# Harvester_Solar.net
KiCad netlist of a schematic drawn in Altium Designer
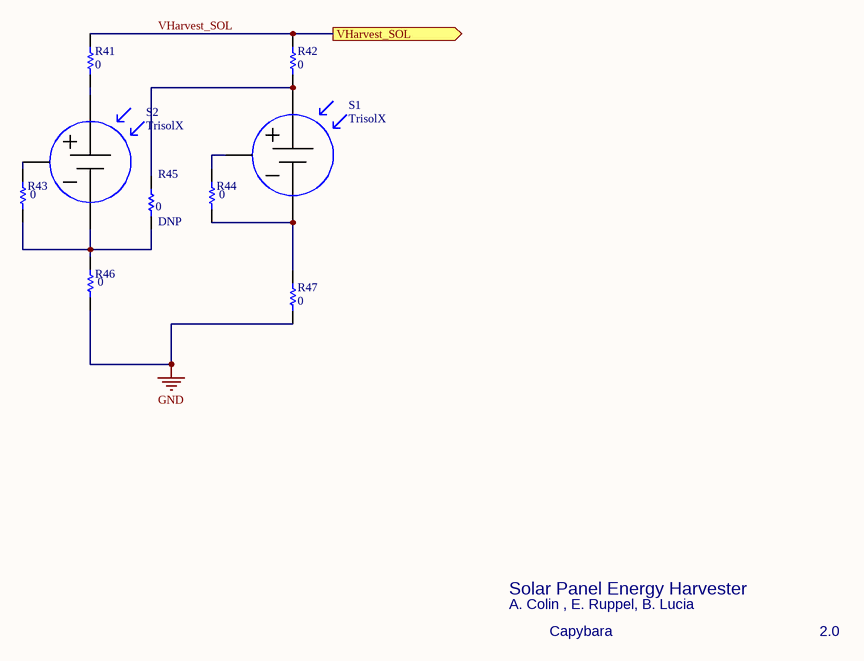
[diagram p0: Harvester_Solar.SchDoc]

(export (version "E")
  (design (tool "Eeschema 10.0.6"))
  (components
    (comp (ref "R41")
      (value "0")
      (footprint "0603")
      (description "Chip Resistor (Surface Mount)")
      (fields
        (field (name "MANUFACTURER") "Yageo")
        (field (name "MANUFACTURER PART NUMBER") "RC0603JR-070RL")
      )
      (libsource (lib "DRP_Basic_2014") (part "Res"))
    )
    (comp (ref "R42")
      (value "0")
      (footprint "0603")
      (description "Chip Resistor (Surface Mount)")
      (fields
        (field (name "MANUFACTURER") "Yageo")
        (field (name "MANUFACTURER PART NUMBER") "RC0603JR-070RL")
      )
      (libsource (lib "DRP_Basic_2014") (part "Res"))
    )
    (comp (ref "R43")
      (value "0")
      (footprint "0603")
      (description "Chip Resistor (Surface Mount)")
      (fields
        (field (name "MANUFACTURER") "Yageo")
        (field (name "MANUFACTURER PART NUMBER") "RC0603JR-070RL")
      )
      (libsource (lib "DRP_Basic_2014") (part "Res"))
    )
    (comp (ref "R44")
      (value "0")
      (footprint "0603")
      (description "Chip Resistor (Surface Mount)")
      (fields
        (field (name "MANUFACTURER") "Yageo")
        (field (name "MANUFACTURER PART NUMBER") "RC0603JR-070RL")
      )
      (libsource (lib "DRP_Basic_2014") (part "Res"))
    )
    (comp (ref "R45")
      (value "DNP")
      (footprint "0603")
      (description "Chip Resistor (Surface Mount)")
      (fields
        (field (name "MANUFACTURER") "Yageo")
        (field (name "MANUFACTURER PART NUMBER") "RC0603JR-070RL")
        (field (name "ALTIUM_VALUE") "0")
      )
      (libsource (lib "DRP_Basic_2014") (part "Res"))
    )
    (comp (ref "R46")
      (value "0")
      (footprint "0603")
      (description "Chip Resistor (Surface Mount)")
      (fields
        (field (name "MANUFACTURER") "Yageo")
        (field (name "MANUFACTURER PART NUMBER") "RC0603JR-070RL")
      )
      (libsource (lib "DRP_Basic_2014") (part "Res"))
    )
    (comp (ref "R47")
      (value "0")
      (footprint "0603")
      (description "Chip Resistor (Surface Mount)")
      (fields
        (field (name "MANUFACTURER") "Yageo")
        (field (name "MANUFACTURER PART NUMBER") "RC0603JR-070RL")
      )
      (libsource (lib "DRP_Basic_2014") (part "Res"))
    )
    (comp (ref "S1")
      (value "TrisolX")
      (footprint "TricoLX - Basic_V3_MIRROR_STRAIGHT_OR_IXYS")
      (description "TrisolX Solar Wings")
      (libsource (lib "Sprite") (part "TrisolX_Solar_Wings"))
    )
    (comp (ref "S2")
      (value "TrisolX")
      (footprint "TricoLX - Basic_V3_MIRROR_STRAIGHT_OR_IXYS")
      (description "TrisolX Solar Wings")
      (libsource (lib "Sprite") (part "TrisolX_Solar_Wings"))
    )
  )
  (nets
    (net (code "1") (name "/VHarvest_SOL") (class "Default")
      (node (ref "R41") (pin "2") (pinfunction "2_2") (pintype "passive"))
      (node (ref "R42") (pin "2") (pinfunction "2_2") (pintype "passive"))
    )
    (net (code "2") (name "GND") (class "Default")
      (node (ref "R46") (pin "1") (pinfunction "1_1") (pintype "passive"))
      (node (ref "R47") (pin "1") (pinfunction "1_1") (pintype "passive"))
    )
    (net (code "3") (name "Net-(S1-OR)") (class "Default")
      (node (ref "R44") (pin "2") (pinfunction "2_2") (pintype "passive"))
      (node (ref "S1") (pin "3") (pinfunction "OR_3") (pintype "passive"))
    )
    (net (code "4") (name "Net-(S1-neg)") (class "Default")
      (node (ref "R44") (pin "1") (pinfunction "1_1") (pintype "passive"))
      (node (ref "R47") (pin "2") (pinfunction "2_2") (pintype "passive"))
      (node (ref "S1") (pin "2") (pinfunction "neg_2") (pintype "passive"))
    )
    (net (code "5") (name "Net-(S1-pos)") (class "Default")
      (node (ref "R42") (pin "1") (pinfunction "1_1") (pintype "passive"))
      (node (ref "R45") (pin "2") (pinfunction "2_2") (pintype "passive"))
      (node (ref "S1") (pin "1") (pinfunction "pos_1") (pintype "passive"))
    )
    (net (code "6") (name "Net-(S2-OR)") (class "Default")
      (node (ref "R43") (pin "2") (pinfunction "2_2") (pintype "passive"))
      (node (ref "S2") (pin "3") (pinfunction "OR_3") (pintype "passive"))
    )
    (net (code "7") (name "Net-(S2-neg)") (class "Default")
      (node (ref "R43") (pin "1") (pinfunction "1_1") (pintype "passive"))
      (node (ref "R45") (pin "1") (pinfunction "1_1") (pintype "passive"))
      (node (ref "R46") (pin "2") (pinfunction "2_2") (pintype "passive"))
      (node (ref "S2") (pin "2") (pinfunction "neg_2") (pintype "passive"))
    )
    (net (code "8") (name "Net-(S2-pos)") (class "Default")
      (node (ref "R41") (pin "1") (pinfunction "1_1") (pintype "passive"))
      (node (ref "S2") (pin "1") (pinfunction "pos_1") (pintype "passive"))
    )
  )
)
